# DATN2022_Power.net
KiCad netlist of a schematic drawn in Altium Designer
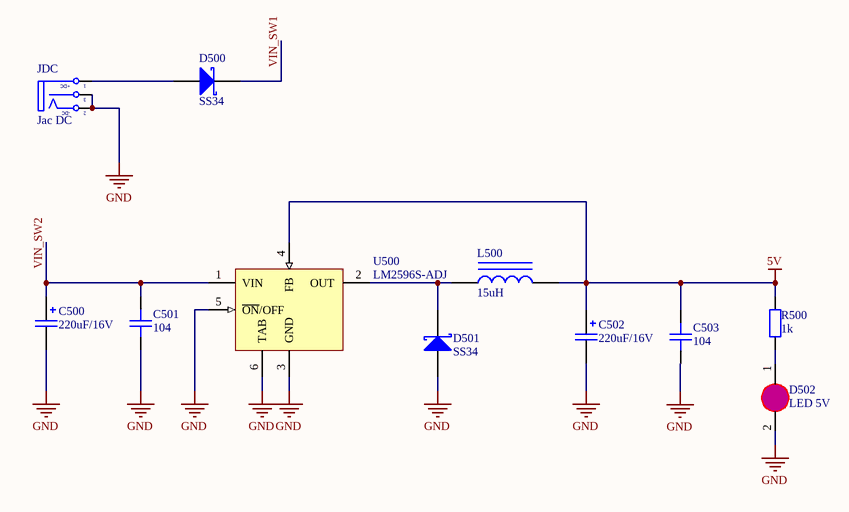
[diagram p0: DATN2022.Power.SchDoc]

(export (version "E")
  (design (tool "Eeschema 10.0.6"))
  (components
    (comp (ref "C500")
      (value "220uF/16V")
      (footprint "CAP_ALUM_SMD_6377_TYPE_D8")
      (description "CAP ALUM 220UF 16V 20% SMD")
      (fields
        (field (name "MANUFACTURER") "Nichicon")
        (field (name "MANUFACTURER PART NUMBER") "UWT1C221MCL1GS")
      )
      (libsource (lib "01.Capacitor") (part "UWT1C221MCL1GS"))
    )
    (comp (ref "C501")
      (value "104")
      (footprint "CAP_CERAMIC_0805(2012mm)")
      (description "Capacitor Ceramic SMD 0805(2012)")
      (fields (field (name "PUBLISHER") "Altium Limited"))
      (libsource (lib "01.Capacitor") (part "Cap Cer 0805 (2012)"))
    )
    (comp (ref "C502")
      (value "220uF/16V")
      (footprint "CAP_ALUM_SMD_6377_TYPE_D8")
      (description "CAP ALUM 220UF 16V 20% SMD")
      (fields
        (field (name "MANUFACTURER") "Nichicon")
        (field (name "MANUFACTURER PART NUMBER") "UWT1C221MCL1GS")
      )
      (libsource (lib "01.Capacitor") (part "UWT1C221MCL1GS"))
    )
    (comp (ref "C503")
      (value "104")
      (footprint "CAP_CERAMIC_0805(2012mm)")
      (description "Capacitor Ceramic SMD 0805(2012)")
      (fields (field (name "PUBLISHER") "Altium Limited"))
      (libsource (lib "01.Capacitor") (part "Cap Cer 0805 (2012)"))
    )
    (comp (ref "D500")
      (value "SS34")
      (footprint "DO214AC_SMA_1808")
      (description "Schottky Diode")
      (fields (field (name "PUBLISHER") "Altium Limited"))
      (libsource (lib "04.Diode_Led") (part "Diode B340A"))
    )
    (comp (ref "D501")
      (value "SS34")
      (footprint "DO214AC_SMA_1808")
      (description "Schottky Diode")
      (fields (field (name "PUBLISHER") "Altium Limited"))
      (libsource (lib "04.Diode_Led") (part "Diode B340A"))
    )
    (comp (ref "D502")
      (value "LED 5V")
      (footprint "LED_0805_RED")
      (description "LED SMD 0805")
      (libsource (lib "04.Diode_Led") (part "LED0805"))
    )
    (comp (ref "JDC")
      (value "Jac DC")
      (footprint "DC0")
      (description "Jac DC input")
      (libsource (lib "Thư Viện Altium FULL HD") (part "DCIN"))
    )
    (comp (ref "L500")
      (value "15uH")
      (footprint "INDUCTOR_SMD_12.5x12.5MM")
      (description "INDUCTOR POWER 15UH 5.0A SMD")
      (fields
        (field (name "MANUFACTURER") "Bourns Inc.")
        (field (name "MANUFACTURER PART NUMBER") "SRR1260-150M")
      )
      (libsource (lib "03.Inductor") (part "SRR1260-150MCT-ND"))
    )
    (comp (ref "R500")
      (value "1k")
      (footprint "RES_0805(2012)")
      (description "Resistor SMD 0805")
      (fields (field (name "PUBLISHER") "Altium Limited"))
      (libsource (lib "02.Resistor") (part "R0805"))
    )
    (comp (ref "U500")
      (value "LM2596S-ADJ")
      (footprint "TO-263-5")
      (description "SIMPLE SWITCHER Power Converter 150 KHz 3A Step-Down Voltage Regulator")
      (fields
        (field (name "MANUFACTURER") "National Semiconductor")
        (field (name "DIGIKEYPARTNUMBER") "LM2596S-ADJ-ND")
        (field (name "PUBLISHER") "Altium Limited")
      )
      (libsource (lib "11.PowerSupply") (part "LM2596S-ADJ"))
    )
  )
  (nets
    (net (code "1") (name "/VIN_SW1") (class "Default")
      (node (ref "D500") (pin "2") (pinfunction "K_2") (pintype "passive"))
    )
    (net (code "2") (name "/VIN_SW2") (class "Default")
      (node (ref "C500") (pin "1") (pinfunction "1_1") (pintype "passive"))
      (node (ref "C501") (pin "2") (pinfunction "2_2") (pintype "passive"))
      (node (ref "U500") (pin "1") (pinfunction "VIN_1") (pintype "power_in"))
    )
    (net (code "3") (name "5V") (class "Default")
      (node (ref "C502") (pin "1") (pinfunction "1_1") (pintype "passive"))
      (node (ref "C503") (pin "2") (pinfunction "2_2") (pintype "passive"))
      (node (ref "L500") (pin "2") (pinfunction "2_2") (pintype "passive"))
      (node (ref "R500") (pin "2") (pinfunction "2_2") (pintype "passive"))
      (node (ref "U500") (pin "4") (pinfunction "FB_4") (pintype "input"))
    )
    (net (code "4") (name "GND") (class "Default")
      (node (ref "C500") (pin "2") (pinfunction "2_2") (pintype "passive"))
      (node (ref "C501") (pin "1") (pinfunction "1_1") (pintype "passive"))
      (node (ref "C502") (pin "2") (pinfunction "2_2") (pintype "passive"))
      (node (ref "C503") (pin "1") (pinfunction "1_1") (pintype "passive"))
      (node (ref "D501") (pin "1") (pinfunction "A_1") (pintype "passive"))
      (node (ref "D502") (pin "2") (pinfunction "K_2") (pintype "passive"))
      (node (ref "JDC") (pin "2") (pinfunction "TN_2") (pintype "passive"))
      (node (ref "JDC") (pin "3") (pinfunction "S_3") (pintype "power_in"))
      (node (ref "U500") (pin "3") (pinfunction "GND_3") (pintype "power_in"))
      (node (ref "U500") (pin "5") (pinfunction "~{ON}/OFF_5") (pintype "input"))
      (node (ref "U500") (pin "6") (pinfunction "TAB_6") (pintype "power_in"))
    )
    (net (code "5") (name "Net-(D500-A)") (class "Default")
      (node (ref "D500") (pin "1") (pinfunction "A_1") (pintype "passive"))
      (node (ref "JDC") (pin "1") (pinfunction "T_1") (pintype "passive"))
    )
    (net (code "6") (name "Net-(D501-K)") (class "Default")
      (node (ref "D501") (pin "2") (pinfunction "K_2") (pintype "passive"))
      (node (ref "L500") (pin "1") (pinfunction "1_1") (pintype "passive"))
      (node (ref "U500") (pin "2") (pinfunction "OUT_2") (pintype "power_in"))
    )
    (net (code "7") (name "Net-(D502-A)") (class "Default")
      (node (ref "D502") (pin "1") (pinfunction "A_1") (pintype "passive"))
      (node (ref "R500") (pin "1") (pinfunction "1_1") (pintype "passive"))
    )
  )
)
